# video_xchng_v4.net
KiCad netlist of a schematic drawn in EAGLE
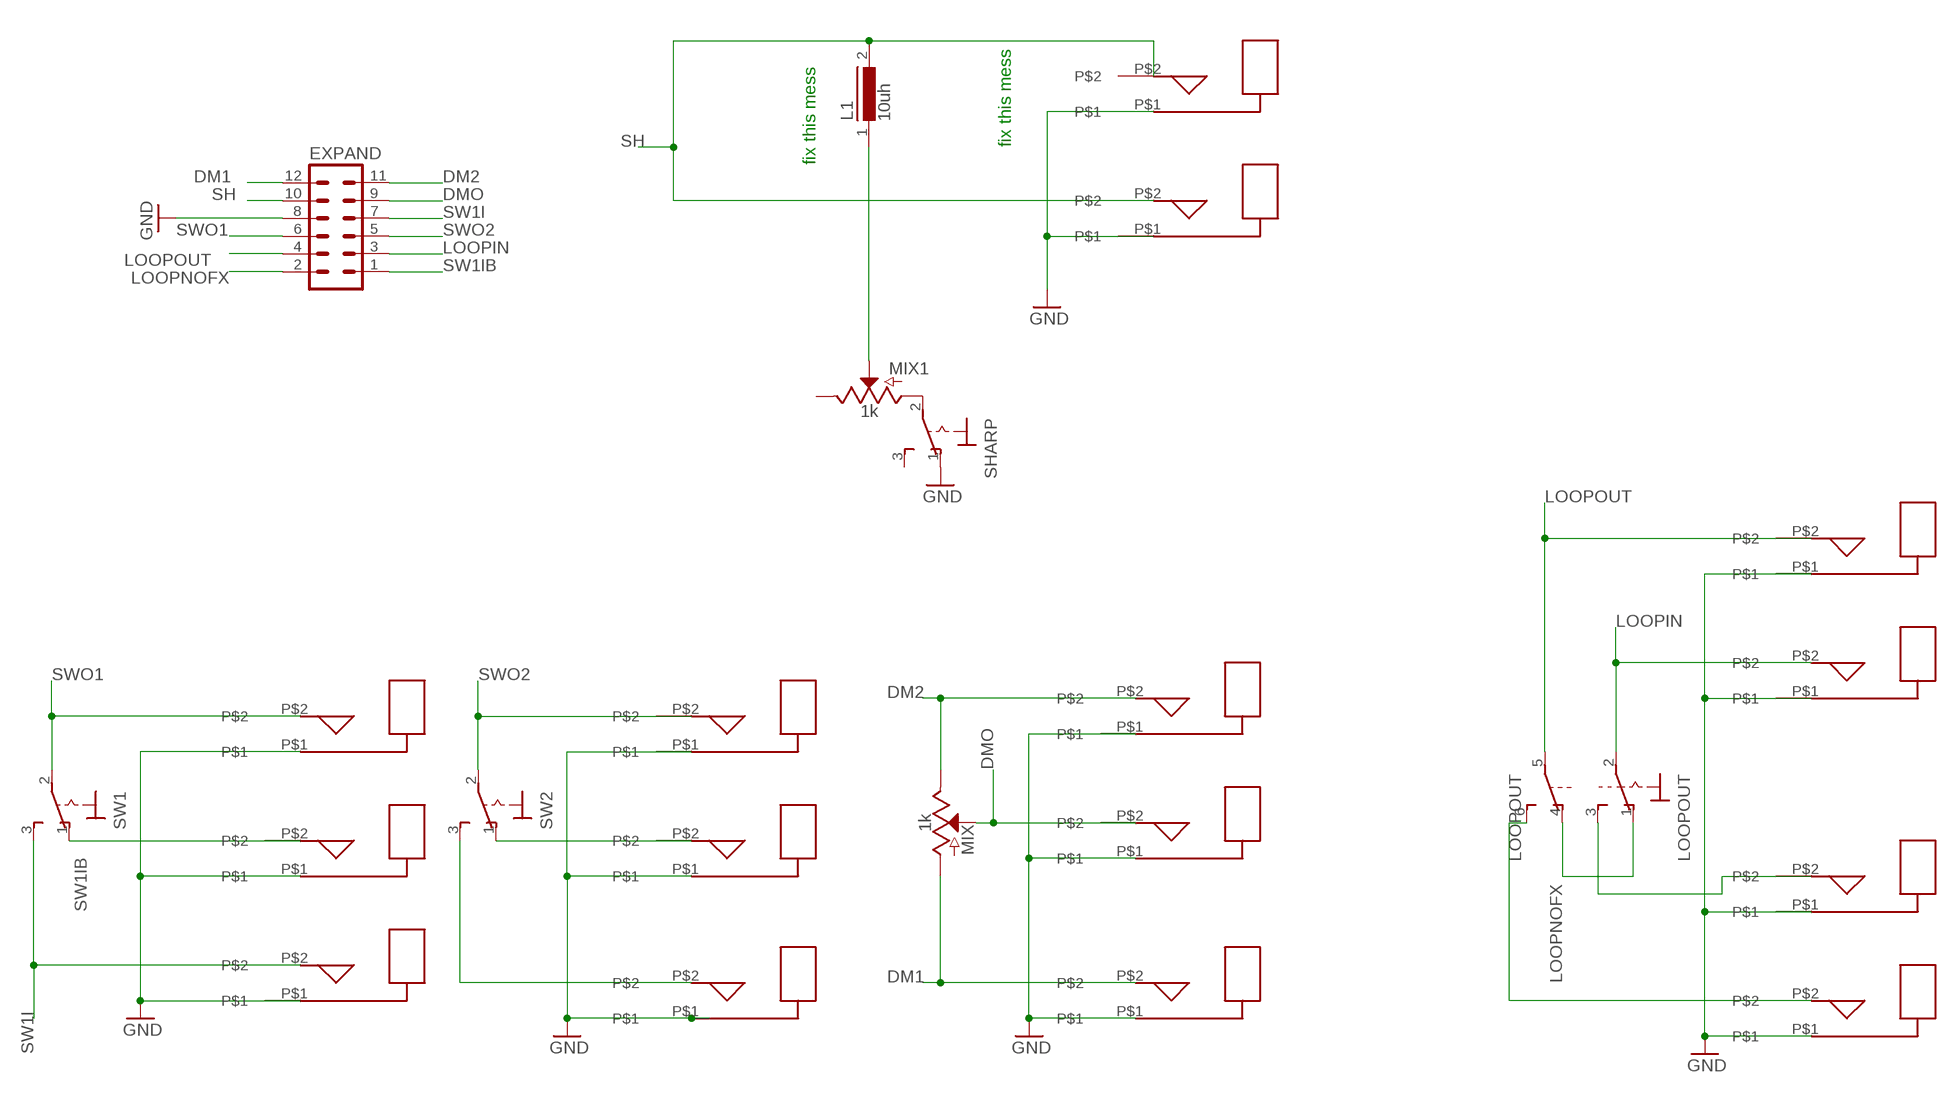
[diagram p0: schematic, sheet 1]

(export (version "E")
  (design (tool "Eeschema 10.0.6"))
  (components
    (comp (ref "EXPAND")
      (value "MA06-2")
      (footprint "eagle-import:MA06-2")
      (libsource (lib "eagle-import") (part "MA06-2"))
    )
    (comp (ref "L1")
      (value "10uh")
      (footprint "eagle-import:LBC15")
      (libsource (lib "eagle-import") (part "LBC15"))
    )
    (comp (ref "LOOPOUT")
      (value "M9040P2")
      (footprint "eagle-import:M9040P2")
      (libsource (lib "eagle-import") (part "M9040P2"))
    )
    (comp (ref "MIX")
      (value "1k")
      (footprint "eagle-import:POT-PTH-ALPS")
      (libsource (lib "eagle-import") (part "POTENTIOMETER-PTH-9MM-1/20W-20%"))
    )
    (comp (ref "MIX1")
      (value "1k")
      (footprint "eagle-import:POT-PTH-ALPS")
      (libsource (lib "eagle-import") (part "POTENTIOMETER-PTH-9MM-1/20W-20%"))
    )
    (comp (ref "SHARP")
      (value "M9040P")
      (footprint "eagle-import:M9040P")
      (libsource (lib "eagle-import") (part "M9040P"))
    )
    (comp (ref "SHARPIN")
      (value "RCJJACK,VERTICAL,PCBMOUNT")
      (footprint "eagle-import:RCJJACK,VERTICAL,PCBMOUNT")
      (libsource (lib "eagle-import") (part "RCJJACK,VERTICAL,PCBMOUNT"))
    )
    (comp (ref "SW1")
      (value "M9040P")
      (footprint "eagle-import:M9040P")
      (libsource (lib "eagle-import") (part "M9040P"))
    )
    (comp (ref "SW2")
      (value "M9040P")
      (footprint "eagle-import:M9040P")
      (libsource (lib "eagle-import") (part "M9040P"))
    )
    (comp (ref "U$1")
      (value "RCJJACK,VERTICAL,PCBMOUNT")
      (footprint "eagle-import:RCJJACK,VERTICAL,PCBMOUNT")
      (libsource (lib "eagle-import") (part "RCJJACK,VERTICAL,PCBMOUNT"))
    )
    (comp (ref "U$2")
      (value "RCJJACK,VERTICAL,PCBMOUNT")
      (footprint "eagle-import:RCJJACK,VERTICAL,PCBMOUNT")
      (libsource (lib "eagle-import") (part "RCJJACK,VERTICAL,PCBMOUNT"))
    )
    (comp (ref "U$3")
      (value "RCJJACK,VERTICAL,PCBMOUNT")
      (footprint "eagle-import:RCJJACK,VERTICAL,PCBMOUNT")
      (libsource (lib "eagle-import") (part "RCJJACK,VERTICAL,PCBMOUNT"))
    )
    (comp (ref "U$4")
      (value "RCJJACK,VERTICAL,PCBMOUNT")
      (footprint "eagle-import:RCJJACK,VERTICAL,PCBMOUNT")
      (libsource (lib "eagle-import") (part "RCJJACK,VERTICAL,PCBMOUNT"))
    )
    (comp (ref "U$5")
      (value "RCJJACK,VERTICAL,PCBMOUNT")
      (footprint "eagle-import:RCJJACK,VERTICAL,PCBMOUNT")
      (libsource (lib "eagle-import") (part "RCJJACK,VERTICAL,PCBMOUNT"))
    )
    (comp (ref "U$6")
      (value "RCJJACK,VERTICAL,PCBMOUNT")
      (footprint "eagle-import:RCJJACK,VERTICAL,PCBMOUNT")
      (libsource (lib "eagle-import") (part "RCJJACK,VERTICAL,PCBMOUNT"))
    )
    (comp (ref "U$7")
      (value "RCJJACK,VERTICAL,PCBMOUNT")
      (footprint "eagle-import:RCJJACK,VERTICAL,PCBMOUNT")
      (libsource (lib "eagle-import") (part "RCJJACK,VERTICAL,PCBMOUNT"))
    )
    (comp (ref "U$8")
      (value "RCJJACK,VERTICAL,PCBMOUNT")
      (footprint "eagle-import:RCJJACK,VERTICAL,PCBMOUNT")
      (libsource (lib "eagle-import") (part "RCJJACK,VERTICAL,PCBMOUNT"))
    )
    (comp (ref "U$9")
      (value "RCJJACK,VERTICAL,PCBMOUNT")
      (footprint "eagle-import:RCJJACK,VERTICAL,PCBMOUNT")
      (libsource (lib "eagle-import") (part "RCJJACK,VERTICAL,PCBMOUNT"))
    )
    (comp (ref "U$10")
      (value "RCJJACK,VERTICAL,PCBMOUNT")
      (footprint "eagle-import:RCJJACK,VERTICAL,PCBMOUNT")
      (libsource (lib "eagle-import") (part "RCJJACK,VERTICAL,PCBMOUNT"))
    )
    (comp (ref "U$11")
      (value "RCJJACK,VERTICAL,PCBMOUNT")
      (footprint "eagle-import:RCJJACK,VERTICAL,PCBMOUNT")
      (libsource (lib "eagle-import") (part "RCJJACK,VERTICAL,PCBMOUNT"))
    )
    (comp (ref "U$12")
      (value "RCJJACK,VERTICAL,PCBMOUNT")
      (footprint "eagle-import:RCJJACK,VERTICAL,PCBMOUNT")
      (libsource (lib "eagle-import") (part "RCJJACK,VERTICAL,PCBMOUNT"))
    )
    (comp (ref "U$13")
      (value "RCJJACK,VERTICAL,PCBMOUNT")
      (footprint "eagle-import:RCJJACK,VERTICAL,PCBMOUNT")
      (libsource (lib "eagle-import") (part "RCJJACK,VERTICAL,PCBMOUNT"))
    )
    (comp (ref "U$15")
      (value "RCJJACK,VERTICAL,PCBMOUNT")
      (footprint "eagle-import:RCJJACK,VERTICAL,PCBMOUNT")
      (libsource (lib "eagle-import") (part "RCJJACK,VERTICAL,PCBMOUNT"))
    )
  )
  (nets
    (net (code "1") (name "/DM1") (class "Default")
      (node (ref "EXPAND") (pin "12") (pinfunction "12_12") (pintype "passive"))
      (node (ref "MIX") (pin "P$3") (pinfunction "A_P$3") (pintype "passive"))
      (node (ref "U$9") (pin "P$2") (pinfunction "P$2_P$2") (pintype "bidirectional"))
    )
    (net (code "2") (name "/DM2") (class "Default")
      (node (ref "EXPAND") (pin "11") (pinfunction "11_11") (pintype "passive"))
      (node (ref "MIX") (pin "P$1") (pinfunction "E_P$1") (pintype "passive"))
      (node (ref "U$7") (pin "P$2") (pinfunction "P$2_P$2") (pintype "bidirectional"))
    )
    (net (code "3") (name "/DMO") (class "Default")
      (node (ref "EXPAND") (pin "9") (pinfunction "9_9") (pintype "passive"))
      (node (ref "MIX") (pin "P$2") (pinfunction "S_P$2") (pintype "passive"))
      (node (ref "U$8") (pin "P$2") (pinfunction "P$2_P$2") (pintype "bidirectional"))
    )
    (net (code "4") (name "/LOOPIN") (class "Default")
      (node (ref "EXPAND") (pin "3") (pinfunction "3_3") (pintype "passive"))
      (node (ref "LOOPOUT") (pin "2") (pinfunction "P_2") (pintype "passive"))
      (node (ref "U$11") (pin "P$2") (pinfunction "P$2_P$2") (pintype "bidirectional"))
    )
    (net (code "5") (name "/LOOPNOFX") (class "Default")
      (node (ref "EXPAND") (pin "2") (pinfunction "2_2") (pintype "passive"))
      (node (ref "LOOPOUT") (pin "1") (pinfunction "O_1") (pintype "passive"))
      (node (ref "LOOPOUT") (pin "4") (pinfunction "O_4") (pintype "passive"))
    )
    (net (code "6") (name "/LOOPOUT") (class "Default")
      (node (ref "EXPAND") (pin "4") (pinfunction "4_4") (pintype "passive"))
      (node (ref "LOOPOUT") (pin "5") (pinfunction "P_5") (pintype "passive"))
      (node (ref "U$10") (pin "P$2") (pinfunction "P$2_P$2") (pintype "bidirectional"))
    )
    (net (code "7") (name "/SH") (class "Default")
      (node (ref "EXPAND") (pin "10") (pinfunction "10_10") (pintype "passive"))
      (node (ref "L1") (pin "2") (pinfunction "2_2") (pintype "passive"))
      (node (ref "SHARPIN") (pin "P$2") (pinfunction "P$2_P$2") (pintype "bidirectional"))
      (node (ref "U$15") (pin "P$2") (pinfunction "P$2_P$2") (pintype "bidirectional"))
    )
    (net (code "8") (name "/SW1I") (class "Default")
      (node (ref "EXPAND") (pin "7") (pinfunction "7_7") (pintype "passive"))
      (node (ref "SW1") (pin "3") (pinfunction "S_3") (pintype "passive"))
      (node (ref "U$3") (pin "P$2") (pinfunction "P$2_P$2") (pintype "bidirectional"))
    )
    (net (code "9") (name "/SW1IB") (class "Default")
      (node (ref "EXPAND") (pin "1") (pinfunction "1_1") (pintype "passive"))
      (node (ref "SW1") (pin "1") (pinfunction "O_1") (pintype "passive"))
      (node (ref "U$2") (pin "P$2") (pinfunction "P$2_P$2") (pintype "bidirectional"))
    )
    (net (code "10") (name "/SWO1") (class "Default")
      (node (ref "EXPAND") (pin "6") (pinfunction "6_6") (pintype "passive"))
      (node (ref "SW1") (pin "2") (pinfunction "P_2") (pintype "passive"))
      (node (ref "U$1") (pin "P$2") (pinfunction "P$2_P$2") (pintype "bidirectional"))
    )
    (net (code "11") (name "/SWO2") (class "Default")
      (node (ref "EXPAND") (pin "5") (pinfunction "5_5") (pintype "passive"))
      (node (ref "SW2") (pin "2") (pinfunction "P_2") (pintype "passive"))
      (node (ref "U$4") (pin "P$2") (pinfunction "P$2_P$2") (pintype "bidirectional"))
    )
    (net (code "12") (name "GND") (class "Default")
      (node (ref "EXPAND") (pin "8") (pinfunction "8_8") (pintype "passive"))
      (node (ref "SHARP") (pin "1") (pinfunction "O_1") (pintype "passive"))
      (node (ref "SHARPIN") (pin "P$1") (pinfunction "P$1_P$1") (pintype "bidirectional"))
      (node (ref "U$1") (pin "P$1") (pinfunction "P$1_P$1") (pintype "bidirectional"))
      (node (ref "U$10") (pin "P$1") (pinfunction "P$1_P$1") (pintype "bidirectional"))
      (node (ref "U$11") (pin "P$1") (pinfunction "P$1_P$1") (pintype "bidirectional"))
      (node (ref "U$12") (pin "P$1") (pinfunction "P$1_P$1") (pintype "bidirectional"))
      (node (ref "U$13") (pin "P$1") (pinfunction "P$1_P$1") (pintype "bidirectional"))
      (node (ref "U$15") (pin "P$1") (pinfunction "P$1_P$1") (pintype "bidirectional"))
      (node (ref "U$2") (pin "P$1") (pinfunction "P$1_P$1") (pintype "bidirectional"))
      (node (ref "U$3") (pin "P$1") (pinfunction "P$1_P$1") (pintype "bidirectional"))
      (node (ref "U$4") (pin "P$1") (pinfunction "P$1_P$1") (pintype "bidirectional"))
      (node (ref "U$5") (pin "P$1") (pinfunction "P$1_P$1") (pintype "bidirectional"))
      (node (ref "U$6") (pin "P$1") (pinfunction "P$1_P$1") (pintype "bidirectional"))
      (node (ref "U$7") (pin "P$1") (pinfunction "P$1_P$1") (pintype "bidirectional"))
      (node (ref "U$8") (pin "P$1") (pinfunction "P$1_P$1") (pintype "bidirectional"))
      (node (ref "U$9") (pin "P$1") (pinfunction "P$1_P$1") (pintype "bidirectional"))
    )
    (net (code "13") (name "Net-(LOOPOUTA-S)") (class "Default")
      (node (ref "LOOPOUT") (pin "3") (pinfunction "S_3") (pintype "passive"))
      (node (ref "U$12") (pin "P$2") (pinfunction "P$2_P$2") (pintype "bidirectional"))
    )
    (net (code "14") (name "Net-(LOOPOUTB-S)") (class "Default")
      (node (ref "LOOPOUT") (pin "6") (pinfunction "S_6") (pintype "passive"))
      (node (ref "U$13") (pin "P$2") (pinfunction "P$2_P$2") (pintype "bidirectional"))
    )
    (net (code "15") (name "Net-(MIX1-A)") (class "Default")
      (node (ref "MIX1") (pin "P$3") (pinfunction "A_P$3") (pintype "passive"))
      (node (ref "SHARP") (pin "2") (pinfunction "P_2") (pintype "passive"))
    )
    (net (code "16") (name "Net-(MIX1-S)") (class "Default")
      (node (ref "L1") (pin "1") (pinfunction "1_1") (pintype "passive"))
      (node (ref "MIX1") (pin "P$2") (pinfunction "S_P$2") (pintype "passive"))
    )
    (net (code "17") (name "Net-(SW2-O)") (class "Default")
      (node (ref "SW2") (pin "1") (pinfunction "O_1") (pintype "passive"))
      (node (ref "U$5") (pin "P$2") (pinfunction "P$2_P$2") (pintype "bidirectional"))
    )
    (net (code "18") (name "Net-(SW2-S)") (class "Default")
      (node (ref "SW2") (pin "3") (pinfunction "S_3") (pintype "passive"))
      (node (ref "U$6") (pin "P$2") (pinfunction "P$2_P$2") (pintype "bidirectional"))
    )
    (net (code "19") (name "unconnected-(MIX1-E-PadP$1)") (class "Default")
      (node (ref "MIX1") (pin "P$1") (pinfunction "E_P$1") (pintype "passive"))
    )
    (net (code "20") (name "unconnected-(SHARP-S-Pad3)") (class "Default")
      (node (ref "SHARP") (pin "3") (pinfunction "S_3") (pintype "passive"))
    )
  )
)
